# GPIO_Raspberry_b.net
KiCad netlist of a schematic drawn in Altium Designer
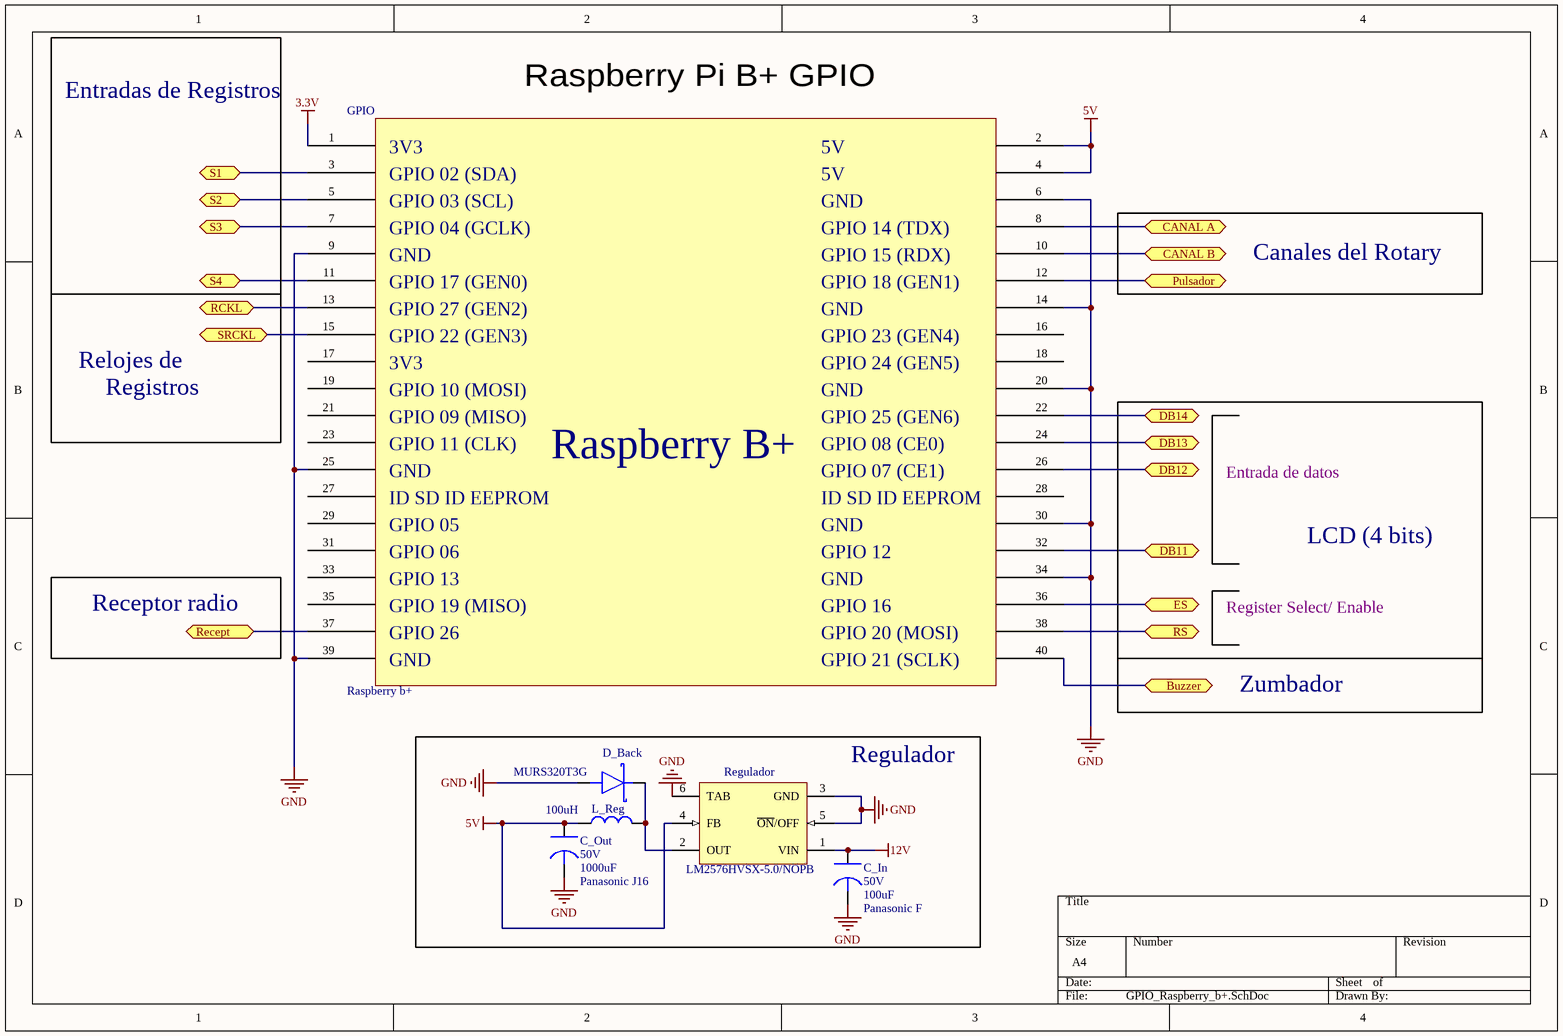
[diagram p0: GPIO_Raspberry_b+.SchDoc]

(export (version "E")
  (design (tool "Eeschema 10.0.6"))
  (components
    (comp (ref "C_In")
      (value "100uF")
      (footprint "Panasonic F Size")
      (description "Condensador Electrolítico SMD")
      (fields
        (field (name "PART NUMBER") "EMV-500ADA101MJA0G")
        (field (name "TOLERANCE") "20%")
        (field (name "VOLTAGE RATING") "50V")
        (field (name "PCB DECAL") "Panasonic F")
        (field (name "AUTHOR") "Jaime Jiménez Ortega")
      )
      (libsource (lib "Libreria_Organo") (part "Panasonic 100uF"))
    )
    (comp (ref "C_Out")
      (value "1000uF")
      (footprint "Panasonic J16 Size")
      (description "Condensador Electrolítico SMD")
      (fields
        (field (name "PART NUMBER") "EMV-500ADA101MJA0G")
        (field (name "TOLERANCE") "20%")
        (field (name "VOLTAGE RATING") "50V")
        (field (name "PCB DECAL") "Panasonic J16")
        (field (name "AUTHOR") "Jaime Jiménez Ortega")
      )
      (libsource (lib "Libreria_Organo") (part "Panasonic 1000uF"))
    )
    (comp (ref "D_Back")
      (value "MURS320T3G")
      (footprint "DO-214AB")
      (description "Surface Mount Schottky-Rectifiers")
      (fields (field (name "AUTHOR") "Jaime Jiménez Ortega"))
      (libsource (lib "Libreria_Organo") (part "MURS320T3G"))
    )
    (comp (ref "GPIO")
      (value "Raspberry b+")
      (footprint "Raspberry")
      (libsource (lib "Libreria_Organo") (part "Raspberry b+"))
    )
    (comp (ref "L_Reg")
      (value "100uH")
      (footprint "DO-5040H 15uH-1400uH")
      (description "Inductor")
      (fields
        (field (name "PART NUMBER") "DO5040H-104ML_")
        (field (name "Comment") "DO-5040H-104ML_")
        (field (name "AUTHOR") "Jaime Jiménez Ortega")
      )
      (libsource (lib "Libreria_Organo") (part "Inductor"))
    )
    (comp (ref "Regulador")
      (value "LM2576HVSX-5.0/NOPB")
      (footprint "TS5B_N_")
      (description "SIMPLE SWITCHER® 3A Step-Down Voltage Regulator, 5-pin TO-263, Pb-Free")
      (fields
        (field (name "MANUFACTURER") "National Semiconductor")
        (field (name "PUBLISHER") "Altium Limited")
      )
      (libsource (lib "Libreria_Organo") (part "LM2576HVSX-5.0/NOPB"))
    )
  )
  (nets
    (net (code "1") (name "/Buzzer") (class "Default")
      (node (ref "GPIO") (pin "40") (pinfunction "40_40") (pintype "passive"))
    )
    (net (code "2") (name "/CANAL A") (class "Default")
      (node (ref "GPIO") (pin "8") (pinfunction "8_8") (pintype "passive"))
    )
    (net (code "3") (name "/CANAL B") (class "Default")
      (node (ref "GPIO") (pin "10") (pinfunction "10_10") (pintype "passive"))
    )
    (net (code "4") (name "/DB11") (class "Default")
      (node (ref "GPIO") (pin "32") (pinfunction "32_32") (pintype "passive"))
    )
    (net (code "5") (name "/DB12") (class "Default")
      (node (ref "GPIO") (pin "26") (pinfunction "26_26") (pintype "passive"))
    )
    (net (code "6") (name "/DB13") (class "Default")
      (node (ref "GPIO") (pin "24") (pinfunction "24_24") (pintype "passive"))
    )
    (net (code "7") (name "/DB14") (class "Default")
      (node (ref "GPIO") (pin "22") (pinfunction "22_22") (pintype "passive"))
    )
    (net (code "8") (name "/ES") (class "Default")
      (node (ref "GPIO") (pin "36") (pinfunction "36_36") (pintype "passive"))
    )
    (net (code "9") (name "/Pulsador") (class "Default")
      (node (ref "GPIO") (pin "12") (pinfunction "12_12") (pintype "passive"))
    )
    (net (code "10") (name "/RCKL") (class "Default")
      (node (ref "GPIO") (pin "13") (pinfunction "13_13") (pintype "passive"))
    )
    (net (code "11") (name "/RS") (class "Default")
      (node (ref "GPIO") (pin "38") (pinfunction "38_38") (pintype "passive"))
    )
    (net (code "12") (name "/Recept") (class "Default")
      (node (ref "GPIO") (pin "37") (pinfunction "37_37") (pintype "passive"))
    )
    (net (code "13") (name "/S1") (class "Default")
      (node (ref "GPIO") (pin "3") (pinfunction "3_3") (pintype "passive"))
    )
    (net (code "14") (name "/S2") (class "Default")
      (node (ref "GPIO") (pin "5") (pinfunction "5_5") (pintype "passive"))
    )
    (net (code "15") (name "/S3") (class "Default")
      (node (ref "GPIO") (pin "7") (pinfunction "7_7") (pintype "passive"))
    )
    (net (code "16") (name "/S4") (class "Default")
      (node (ref "GPIO") (pin "11") (pinfunction "11_11") (pintype "passive"))
    )
    (net (code "17") (name "/SRCKL") (class "Default")
      (node (ref "GPIO") (pin "15") (pinfunction "15_15") (pintype "passive"))
    )
    (net (code "18") (name "3.3V") (class "Default")
      (node (ref "GPIO") (pin "1") (pinfunction "1_1") (pintype "passive"))
    )
    (net (code "19") (name "5V") (class "Default")
      (node (ref "C_Out") (pin "1") (pintype "power_in"))
      (node (ref "GPIO") (pin "2") (pinfunction "2_2") (pintype "passive"))
      (node (ref "GPIO") (pin "4") (pinfunction "4_4") (pintype "passive"))
      (node (ref "L_Reg") (pin "1") (pintype "passive"))
      (node (ref "Regulador") (pin "4") (pinfunction "FB_4") (pintype "input"))
    )
    (net (code "20") (name "12V") (class "Default")
      (node (ref "C_In") (pin "1") (pintype "power_in"))
      (node (ref "Regulador") (pin "1") (pinfunction "VIN_1") (pintype "power_in"))
    )
    (net (code "21") (name "GND") (class "Default")
      (node (ref "C_In") (pin "2") (pintype "power_in"))
      (node (ref "C_Out") (pin "2") (pintype "power_in"))
      (node (ref "D_Back") (pin "A") (pinfunction "A_A") (pintype "passive"))
      (node (ref "GPIO") (pin "14") (pinfunction "14_14") (pintype "passive"))
      (node (ref "GPIO") (pin "20") (pinfunction "20_20") (pintype "passive"))
      (node (ref "GPIO") (pin "25") (pinfunction "25_25") (pintype "passive"))
      (node (ref "GPIO") (pin "30") (pinfunction "30_30") (pintype "passive"))
      (node (ref "GPIO") (pin "34") (pinfunction "34_34") (pintype "passive"))
      (node (ref "GPIO") (pin "39") (pinfunction "39_39") (pintype "passive"))
      (node (ref "GPIO") (pin "6") (pinfunction "6_6") (pintype "passive"))
      (node (ref "GPIO") (pin "9") (pinfunction "9_9") (pintype "passive"))
      (node (ref "Regulador") (pin "3") (pinfunction "GND_3") (pintype "power_in"))
      (node (ref "Regulador") (pin "5") (pinfunction "~{ON}/OFF_5") (pintype "input"))
      (node (ref "Regulador") (pin "6") (pinfunction "TAB_6") (pintype "power_in"))
    )
    (net (code "22") (name "Net-(Regulador-OUT)") (class "Default")
      (node (ref "D_Back") (pin "K") (pinfunction "K_K") (pintype "passive"))
      (node (ref "L_Reg") (pin "2") (pintype "passive"))
      (node (ref "Regulador") (pin "2") (pinfunction "OUT_2") (pintype "power_in"))
    )
    (net (code "23") (name "unconnected-(GPIO-Pad16)") (class "Default")
      (node (ref "GPIO") (pin "16") (pinfunction "16_16") (pintype "passive"))
    )
    (net (code "24") (name "unconnected-(GPIO-Pad17)") (class "Default")
      (node (ref "GPIO") (pin "17") (pinfunction "17_17") (pintype "passive"))
    )
    (net (code "25") (name "unconnected-(GPIO-Pad18)") (class "Default")
      (node (ref "GPIO") (pin "18") (pinfunction "18_18") (pintype "passive"))
    )
    (net (code "26") (name "unconnected-(GPIO-Pad19)") (class "Default")
      (node (ref "GPIO") (pin "19") (pinfunction "19_19") (pintype "passive"))
    )
    (net (code "27") (name "unconnected-(GPIO-Pad21)") (class "Default")
      (node (ref "GPIO") (pin "21") (pinfunction "21_21") (pintype "passive"))
    )
    (net (code "28") (name "unconnected-(GPIO-Pad23)") (class "Default")
      (node (ref "GPIO") (pin "23") (pinfunction "23_23") (pintype "passive"))
    )
    (net (code "29") (name "unconnected-(GPIO-Pad27)") (class "Default")
      (node (ref "GPIO") (pin "27") (pinfunction "27_27") (pintype "passive"))
    )
    (net (code "30") (name "unconnected-(GPIO-Pad28)") (class "Default")
      (node (ref "GPIO") (pin "28") (pinfunction "28_28") (pintype "passive"))
    )
    (net (code "31") (name "unconnected-(GPIO-Pad29)") (class "Default")
      (node (ref "GPIO") (pin "29") (pinfunction "29_29") (pintype "passive"))
    )
    (net (code "32") (name "unconnected-(GPIO-Pad31)") (class "Default")
      (node (ref "GPIO") (pin "31") (pinfunction "31_31") (pintype "passive"))
    )
    (net (code "33") (name "unconnected-(GPIO-Pad33)") (class "Default")
      (node (ref "GPIO") (pin "33") (pinfunction "33_33") (pintype "passive"))
    )
    (net (code "34") (name "unconnected-(GPIO-Pad35)") (class "Default")
      (node (ref "GPIO") (pin "35") (pinfunction "35_35") (pintype "passive"))
    )
  )
)
